# ThermalExtSens.net
KiCad netlist of a schematic drawn in Altium Designer
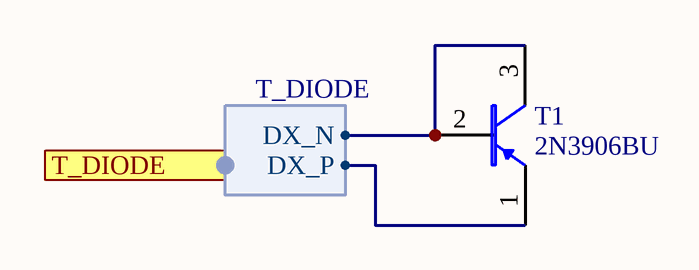
[diagram p0: ThermalExtSens.SchDoc]

(export (version "E")
  (design (tool "Eeschema 10.0.6"))
  (components
    (comp (ref "T1")
      (value "2N3906BU")
      (footprint "TO-92-3")
      (description "Bipolartransistor, PNP")
      (fields
        (field (name "MANUFACTURER") "onsemi")
        (field (name "LCSC PART NUMBER") "C124483")
        (field (name "CREATED FROM") "MGeier")
      )
      (libsource (lib "user") (part "PNP-1E2B3C"))
    )
  )
  (nets
    (net (code "2") (name "/DX_N") (class "Default")
      (node (ref "T1") (pin "2") (pinfunction "BASIS_2") (pintype "passive"))
      (node (ref "T1") (pin "3") (pinfunction "COLLECTOR_3") (pintype "passive"))
    )
    (net (code "3") (name "/DX_P") (class "Default")
      (node (ref "T1") (pin "1") (pinfunction "EMITTER_1") (pintype "passive"))
    )
  )
)
